# VTM_Ethernet_Module.net
KiCad netlist of a schematic drawn in Altium Designer
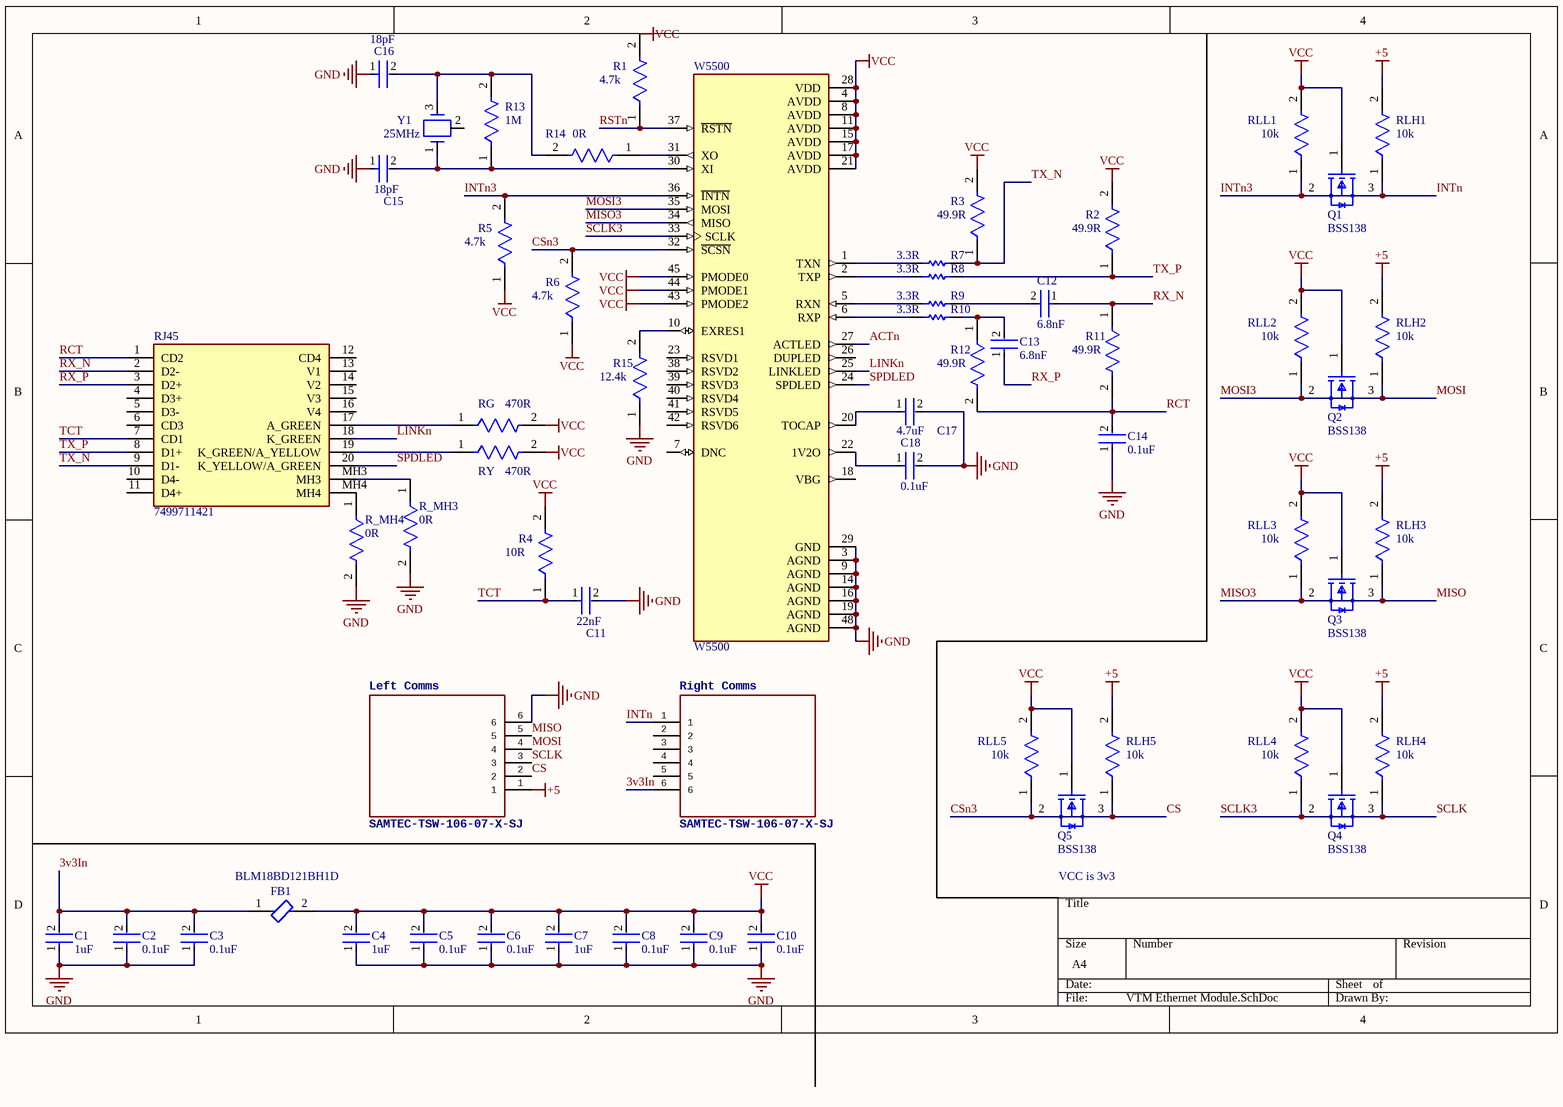
[diagram p0: VTM Ethernet Module.SchDoc]

(export (version "E")
  (design (tool "Eeschema 10.0.6"))
  (components
    (comp (ref "C1")
      (value "1uF")
      (footprint "FP-C0805C-DN-MFG")
      (description "CAP CER 18PF 25V 20% NP0 0805")
      (fields
        (field (name "OCTOPART") "https://octopart.com/c0805c180m3gactu-kemet-17137232")
        (field (name "TOLERANCE") "0.2")
      )
      (libsource (lib "Altium Content Vault") (part "b4654b650e69147ec39a6b967a45e02"))
    )
    (comp (ref "C2")
      (value "0.1uF")
      (footprint "FP-C0805C-DN-MFG")
      (description "CAP CER 18PF 25V 20% NP0 0805")
      (fields
        (field (name "OCTOPART") "https://octopart.com/c0805c180m3gactu-kemet-17137232")
        (field (name "TOLERANCE") "0.2")
      )
      (libsource (lib "Altium Content Vault") (part "b4654b650e69147ec39a6b967a45e02"))
    )
    (comp (ref "C3")
      (value "0.1uF")
      (footprint "FP-C0805C-DN-MFG")
      (description "CAP CER 18PF 25V 20% NP0 0805")
      (fields
        (field (name "OCTOPART") "https://octopart.com/c0805c180m3gactu-kemet-17137232")
        (field (name "TOLERANCE") "0.2")
      )
      (libsource (lib "Altium Content Vault") (part "b4654b650e69147ec39a6b967a45e02"))
    )
    (comp (ref "C4")
      (value "1uF")
      (footprint "FP-C0805C-DN-MFG")
      (description "CAP CER 18PF 25V 20% NP0 0805")
      (fields
        (field (name "OCTOPART") "https://octopart.com/c0805c180m3gactu-kemet-17137232")
        (field (name "TOLERANCE") "0.2")
      )
      (libsource (lib "Altium Content Vault") (part "b4654b650e69147ec39a6b967a45e02"))
    )
    (comp (ref "C5")
      (value "0.1uF")
      (footprint "FP-C0805C-DN-MFG")
      (description "CAP CER 18PF 25V 20% NP0 0805")
      (fields
        (field (name "OCTOPART") "https://octopart.com/c0805c180m3gactu-kemet-17137232")
        (field (name "TOLERANCE") "0.2")
      )
      (libsource (lib "Altium Content Vault") (part "b4654b650e69147ec39a6b967a45e02"))
    )
    (comp (ref "C6")
      (value "0.1uF")
      (footprint "FP-C0805C-DN-MFG")
      (description "CAP CER 18PF 25V 20% NP0 0805")
      (fields
        (field (name "OCTOPART") "https://octopart.com/c0805c180m3gactu-kemet-17137232")
        (field (name "TOLERANCE") "0.2")
      )
      (libsource (lib "Altium Content Vault") (part "b4654b650e69147ec39a6b967a45e02"))
    )
    (comp (ref "C7")
      (value "1uF")
      (footprint "FP-C0805C-DN-MFG")
      (description "CAP CER 18PF 25V 20% NP0 0805")
      (fields
        (field (name "OCTOPART") "https://octopart.com/c0805c180m3gactu-kemet-17137232")
        (field (name "TOLERANCE") "0.2")
      )
      (libsource (lib "Altium Content Vault") (part "b4654b650e69147ec39a6b967a45e02"))
    )
    (comp (ref "C8")
      (value "0.1uF")
      (footprint "FP-C0805C-DN-MFG")
      (description "CAP CER 18PF 25V 20% NP0 0805")
      (fields
        (field (name "OCTOPART") "https://octopart.com/c0805c180m3gactu-kemet-17137232")
        (field (name "TOLERANCE") "0.2")
      )
      (libsource (lib "Altium Content Vault") (part "b4654b650e69147ec39a6b967a45e02"))
    )
    (comp (ref "C9")
      (value "0.1uF")
      (footprint "FP-C0805C-DN-MFG")
      (description "CAP CER 18PF 25V 20% NP0 0805")
      (fields
        (field (name "OCTOPART") "https://octopart.com/c0805c180m3gactu-kemet-17137232")
        (field (name "TOLERANCE") "0.2")
      )
      (libsource (lib "Altium Content Vault") (part "b4654b650e69147ec39a6b967a45e02"))
    )
    (comp (ref "C10")
      (value "0.1uF")
      (footprint "FP-C0805C-DN-MFG")
      (description "CAP CER 18PF 25V 20% NP0 0805")
      (fields
        (field (name "OCTOPART") "https://octopart.com/c0805c180m3gactu-kemet-17137232")
        (field (name "TOLERANCE") "0.2")
      )
      (libsource (lib "Altium Content Vault") (part "b4654b650e69147ec39a6b967a45e02"))
    )
    (comp (ref "C11")
      (value "22nF")
      (footprint "FP-C0805C-DN-MFG")
      (description "CAP CER 18PF 25V 20% NP0 0805")
      (fields
        (field (name "OCTOPART") "https://octopart.com/c0805c180m3gactu-kemet-17137232")
        (field (name "TOLERANCE") "0.2")
      )
      (libsource (lib "Altium Content Vault") (part "b4654b650e69147ec39a6b967a45e02"))
    )
    (comp (ref "C12")
      (value "6.8nF")
      (footprint "FP-C0805C-DN-MFG")
      (description "CAP CER 18PF 25V 20% NP0 0805")
      (fields
        (field (name "OCTOPART") "https://octopart.com/c0805c180m3gactu-kemet-17137232")
        (field (name "TOLERANCE") "0.2")
      )
      (libsource (lib "Altium Content Vault") (part "b4654b650e69147ec39a6b967a45e02"))
    )
    (comp (ref "C13")
      (value "6.8nF")
      (footprint "FP-C0805C-DN-MFG")
      (description "CAP CER 18PF 25V 20% NP0 0805")
      (fields
        (field (name "OCTOPART") "https://octopart.com/c0805c180m3gactu-kemet-17137232")
        (field (name "TOLERANCE") "0.2")
      )
      (libsource (lib "Altium Content Vault") (part "b4654b650e69147ec39a6b967a45e02"))
    )
    (comp (ref "C14")
      (value "0.1uF")
      (footprint "FP-C0805C-DN-MFG")
      (description "CAP CER 18PF 25V 20% NP0 0805")
      (fields
        (field (name "OCTOPART") "https://octopart.com/c0805c180m3gactu-kemet-17137232")
        (field (name "TOLERANCE") "0.2")
      )
      (libsource (lib "Altium Content Vault") (part "b4654b650e69147ec39a6b967a45e02"))
    )
    (comp (ref "C15")
      (value "18pF")
      (footprint "FP-C0805C-DN-MFG")
      (description "CAP CER 18PF 25V 20% NP0 0805")
      (fields
        (field (name "OCTOPART") "https://octopart.com/c0805c180m3gactu-kemet-17137232")
        (field (name "TOLERANCE") "0.2")
      )
      (libsource (lib "Altium Content Vault") (part "b4654b650e69147ec39a6b967a45e02"))
    )
    (comp (ref "C16")
      (value "18pF")
      (footprint "FP-C0805C-DN-MFG")
      (description "CAP CER 18PF 25V 20% NP0 0805")
      (fields
        (field (name "OCTOPART") "https://octopart.com/c0805c180m3gactu-kemet-17137232")
        (field (name "TOLERANCE") "0.2")
      )
      (libsource (lib "Altium Content Vault") (part "b4654b650e69147ec39a6b967a45e02"))
    )
    (comp (ref "C17")
      (value "4.7uF")
      (footprint "FP-C0805C-DN-MFG")
      (description "CAP CER 18PF 25V 20% NP0 0805")
      (fields
        (field (name "OCTOPART") "https://octopart.com/c0805c180m3gactu-kemet-17137232")
        (field (name "TOLERANCE") "0.2")
      )
      (libsource (lib "Altium Content Vault") (part "b4654b650e69147ec39a6b967a45e02"))
    )
    (comp (ref "C18")
      (value "0.1uF")
      (footprint "FP-C0805C-DN-MFG")
      (description "CAP CER 18PF 25V 20% NP0 0805")
      (fields
        (field (name "OCTOPART") "https://octopart.com/c0805c180m3gactu-kemet-17137232")
        (field (name "TOLERANCE") "0.2")
      )
      (libsource (lib "Altium Content Vault") (part "b4654b650e69147ec39a6b967a45e02"))
    )
    (comp (ref "FB1")
      (value "BLM18BD121BH1D")
      (footprint "FP-BLM18-0_15-t0_8-MFG")
      (description "Chip Ferrite Bead, 0603, 120Ω @ 100MHz, 0.4Ω, 25%, 300mA")
      (libsource (lib "Altium Content Vault") (part "5f30dd21d616792df468990f7003faa"))
    )
    (comp (ref "Left Comms")
      (value "SAMTEC-TSW-106-07-X-SJ")
      (footprint "SAMTEC-TSW-106-07-X-S")
      (libsource (lib "TSW-106-07-F-S") (part "SAMTEC-TSW-106-07-X-SJ"))
    )
    (comp (ref "Q1")
      (value "BSS138")
      (footprint "FP-318-08-IPC_B")
      (description "MOSFET N-CH 50V 220MA SOT-23")
      (libsource (lib "Altium Content Vault") (part "3b9c635fedb024a5347a57b145af9cc"))
    )
    (comp (ref "Q2")
      (value "BSS138")
      (footprint "FP-318-08-IPC_B")
      (description "MOSFET N-CH 50V 220MA SOT-23")
      (libsource (lib "Altium Content Vault") (part "3b9c635fedb024a5347a57b145af9cc"))
    )
    (comp (ref "Q3")
      (value "BSS138")
      (footprint "FP-318-08-IPC_B")
      (description "MOSFET N-CH 50V 220MA SOT-23")
      (libsource (lib "Altium Content Vault") (part "3b9c635fedb024a5347a57b145af9cc"))
    )
    (comp (ref "Q4")
      (value "BSS138")
      (footprint "FP-318-08-IPC_B")
      (description "MOSFET N-CH 50V 220MA SOT-23")
      (libsource (lib "Altium Content Vault") (part "3b9c635fedb024a5347a57b145af9cc"))
    )
    (comp (ref "Q5")
      (value "BSS138")
      (footprint "FP-318-08-IPC_B")
      (description "MOSFET N-CH 50V 220MA SOT-23")
      (libsource (lib "Altium Content Vault") (part "3b9c635fedb024a5347a57b145af9cc"))
    )
    (comp (ref "R1")
      (value "4.7k")
      (footprint "FP-CPF0805-MFG")
      (description "RES SMD 1.6M OHM 0.1% 1/10W 0805")
      (fields (field (name "TOLERANCE") "0.1%"))
      (libsource (lib "Altium Content Vault") (part "1029c3af85768c4190bb7ad29bc67b5"))
    )
    (comp (ref "R2")
      (value "49.9R")
      (footprint "FP-CPF0805-MFG")
      (description "RES SMD 1.6M OHM 0.1% 1/10W 0805")
      (fields (field (name "TOLERANCE") "0.1%"))
      (libsource (lib "Altium Content Vault") (part "1029c3af85768c4190bb7ad29bc67b5"))
    )
    (comp (ref "R3")
      (value "49.9R")
      (footprint "FP-CPF0805-MFG")
      (description "RES SMD 1.6M OHM 0.1% 1/10W 0805")
      (fields (field (name "TOLERANCE") "0.1%"))
      (libsource (lib "Altium Content Vault") (part "1029c3af85768c4190bb7ad29bc67b5"))
    )
    (comp (ref "R4")
      (value "10R")
      (footprint "FP-CPF0805-MFG")
      (description "RES SMD 1.6M OHM 0.1% 1/10W 0805")
      (fields (field (name "TOLERANCE") "0.1%"))
      (libsource (lib "Altium Content Vault") (part "1029c3af85768c4190bb7ad29bc67b5"))
    )
    (comp (ref "R5")
      (value "4.7k")
      (footprint "FP-CPF0805-MFG")
      (description "RES SMD 1.6M OHM 0.1% 1/10W 0805")
      (fields (field (name "TOLERANCE") "0.1%"))
      (libsource (lib "Altium Content Vault") (part "1029c3af85768c4190bb7ad29bc67b5"))
    )
    (comp (ref "R6")
      (value "4.7k")
      (footprint "FP-CPF0805-MFG")
      (description "RES SMD 1.6M OHM 0.1% 1/10W 0805")
      (fields (field (name "TOLERANCE") "0.1%"))
      (libsource (lib "Altium Content Vault") (part "1029c3af85768c4190bb7ad29bc67b5"))
    )
    (comp (ref "R7")
      (value "3.3R")
      (footprint "RESC3216X70X50LL05T20")
      (fields (field (name "PART NUMBER") "ERJ-8RQF3R3V") (field (name "MANUFACTURER") "Panasonic"))
      (libsource (lib "Altium Content Vault") (part "RES"))
    )
    (comp (ref "R8")
      (value "3.3R")
      (footprint "RESC3216X70X50LL05T20")
      (fields (field (name "PART NUMBER") "ERJ-8RQF3R3V") (field (name "MANUFACTURER") "Panasonic"))
      (libsource (lib "Altium Content Vault") (part "RES"))
    )
    (comp (ref "R9")
      (value "3.3R")
      (footprint "RESC3216X70X50LL05T20")
      (fields (field (name "PART NUMBER") "ERJ-8RQF3R3V") (field (name "MANUFACTURER") "Panasonic"))
      (libsource (lib "Altium Content Vault") (part "RES"))
    )
    (comp (ref "R10")
      (value "3.3R")
      (footprint "RESC3216X70X50LL05T20")
      (fields (field (name "PART NUMBER") "ERJ-8RQF3R3V") (field (name "MANUFACTURER") "Panasonic"))
      (libsource (lib "Altium Content Vault") (part "RES"))
    )
    (comp (ref "R11")
      (value "49.9R")
      (footprint "FP-CPF0805-MFG")
      (description "RES SMD 1.6M OHM 0.1% 1/10W 0805")
      (fields (field (name "TOLERANCE") "0.1%"))
      (libsource (lib "Altium Content Vault") (part "1029c3af85768c4190bb7ad29bc67b5"))
    )
    (comp (ref "R12")
      (value "49.9R")
      (footprint "FP-CPF0805-MFG")
      (description "RES SMD 1.6M OHM 0.1% 1/10W 0805")
      (fields (field (name "TOLERANCE") "0.1%"))
      (libsource (lib "Altium Content Vault") (part "1029c3af85768c4190bb7ad29bc67b5"))
    )
    (comp (ref "R13")
      (value "1M")
      (footprint "FP-CPF0805-MFG")
      (description "RES SMD 1.6M OHM 0.1% 1/10W 0805")
      (fields (field (name "TOLERANCE") "0.1%"))
      (libsource (lib "Altium Content Vault") (part "1029c3af85768c4190bb7ad29bc67b5"))
    )
    (comp (ref "R14")
      (value "0R")
      (footprint "FP-CPF0805-MFG")
      (description "RES SMD 1.6M OHM 0.1% 1/10W 0805")
      (fields (field (name "TOLERANCE") "0.1%"))
      (libsource (lib "Altium Content Vault") (part "1029c3af85768c4190bb7ad29bc67b5"))
    )
    (comp (ref "R15")
      (value "12.4k")
      (footprint "FP-CPF0805-MFG")
      (description "RES SMD 1.6M OHM 0.1% 1/10W 0805")
      (fields (field (name "TOLERANCE") "0.1%"))
      (libsource (lib "Altium Content Vault") (part "1029c3af85768c4190bb7ad29bc67b5"))
    )
    (comp (ref "RG")
      (value "470R")
      (footprint "FP-CPF0805-MFG")
      (description "RES SMD 1.6M OHM 0.1% 1/10W 0805")
      (fields (field (name "TOLERANCE") "0.1%"))
      (libsource (lib "Altium Content Vault") (part "1029c3af85768c4190bb7ad29bc67b5"))
    )
    (comp (ref "Right Comms")
      (value "SAMTEC-TSW-106-07-X-SJ")
      (footprint "SAMTEC-TSW-106-07-X-S")
      (libsource (lib "TSW-106-07-F-S") (part "SAMTEC-TSW-106-07-X-SJ"))
    )
    (comp (ref "RJ45")
      (value "7499711421")
      (footprint "SamacSys:7499711421")
      (description "Connector")
      (fields (field (name "MOUSER PART NUMBER") "710-7499711421"))
      (libsource (lib "*") (part "7499711421"))
    )
    (comp (ref "RLH1")
      (value "10k")
      (footprint "FP-CPF0805-MFG")
      (description "RES SMD 1.6M OHM 0.1% 1/10W 0805")
      (fields (field (name "TOLERANCE") "0.1%"))
      (libsource (lib "Altium Content Vault") (part "1029c3af85768c4190bb7ad29bc67b5"))
    )
    (comp (ref "RLH2")
      (value "10k")
      (footprint "FP-CPF0805-MFG")
      (description "RES SMD 1.6M OHM 0.1% 1/10W 0805")
      (fields (field (name "TOLERANCE") "0.1%"))
      (libsource (lib "Altium Content Vault") (part "1029c3af85768c4190bb7ad29bc67b5"))
    )
    (comp (ref "RLH3")
      (value "10k")
      (footprint "FP-CPF0805-MFG")
      (description "RES SMD 1.6M OHM 0.1% 1/10W 0805")
      (fields (field (name "TOLERANCE") "0.1%"))
      (libsource (lib "Altium Content Vault") (part "1029c3af85768c4190bb7ad29bc67b5"))
    )
    (comp (ref "RLH4")
      (value "10k")
      (footprint "FP-CPF0805-MFG")
      (description "RES SMD 1.6M OHM 0.1% 1/10W 0805")
      (fields (field (name "TOLERANCE") "0.1%"))
      (libsource (lib "Altium Content Vault") (part "1029c3af85768c4190bb7ad29bc67b5"))
    )
    (comp (ref "RLH5")
      (value "10k")
      (footprint "FP-CPF0805-MFG")
      (description "RES SMD 1.6M OHM 0.1% 1/10W 0805")
      (fields (field (name "TOLERANCE") "0.1%"))
      (libsource (lib "Altium Content Vault") (part "1029c3af85768c4190bb7ad29bc67b5"))
    )
    (comp (ref "RLL1")
      (value "10k")
      (footprint "FP-CPF0805-MFG")
      (description "RES SMD 1.6M OHM 0.1% 1/10W 0805")
      (fields (field (name "TOLERANCE") "0.1%"))
      (libsource (lib "Altium Content Vault") (part "1029c3af85768c4190bb7ad29bc67b5"))
    )
    (comp (ref "RLL2")
      (value "10k")
      (footprint "FP-CPF0805-MFG")
      (description "RES SMD 1.6M OHM 0.1% 1/10W 0805")
      (fields (field (name "TOLERANCE") "0.1%"))
      (libsource (lib "Altium Content Vault") (part "1029c3af85768c4190bb7ad29bc67b5"))
    )
    (comp (ref "RLL3")
      (value "10k")
      (footprint "FP-CPF0805-MFG")
      (description "RES SMD 1.6M OHM 0.1% 1/10W 0805")
      (fields (field (name "TOLERANCE") "0.1%"))
      (libsource (lib "Altium Content Vault") (part "1029c3af85768c4190bb7ad29bc67b5"))
    )
    (comp (ref "RLL4")
      (value "10k")
      (footprint "FP-CPF0805-MFG")
      (description "RES SMD 1.6M OHM 0.1% 1/10W 0805")
      (fields (field (name "TOLERANCE") "0.1%"))
      (libsource (lib "Altium Content Vault") (part "1029c3af85768c4190bb7ad29bc67b5"))
    )
    (comp (ref "RLL5")
      (value "10k")
      (footprint "FP-CPF0805-MFG")
      (description "RES SMD 1.6M OHM 0.1% 1/10W 0805")
      (fields (field (name "TOLERANCE") "0.1%"))
      (libsource (lib "Altium Content Vault") (part "1029c3af85768c4190bb7ad29bc67b5"))
    )
    (comp (ref "RY")
      (value "470R")
      (footprint "FP-CPF0805-MFG")
      (description "RES SMD 1.6M OHM 0.1% 1/10W 0805")
      (fields (field (name "TOLERANCE") "0.1%"))
      (libsource (lib "Altium Content Vault") (part "1029c3af85768c4190bb7ad29bc67b5"))
    )
    (comp (ref "R_MH3")
      (value "0R")
      (footprint "FP-CPF0805-MFG")
      (description "RES SMD 1.6M OHM 0.1% 1/10W 0805")
      (fields (field (name "TOLERANCE") "0.1%"))
      (libsource (lib "Altium Content Vault") (part "1029c3af85768c4190bb7ad29bc67b5"))
    )
    (comp (ref "R_MH4")
      (value "0R")
      (footprint "FP-CPF0805-MFG")
      (description "RES SMD 1.6M OHM 0.1% 1/10W 0805")
      (fields (field (name "TOLERANCE") "0.1%"))
      (libsource (lib "Altium Content Vault") (part "1029c3af85768c4190bb7ad29bc67b5"))
    )
    (comp (ref "W5500")
      (value "W5500")
      (footprint "QFP50P900X900X160-48N")
      (description "Ethernet Controller 10/100 Base-T/TX PHY SPI Interface 48-LQFP (7x7)")
      (fields (field (name "MF") "WIZnet"))
      (libsource (lib "W5500") (part "W5500"))
    )
    (comp (ref "Y1")
      (value "25MHz")
      (footprint "ECS-4X-3IL")
      (description "CRYSTAL 8.00 MHZ 20PF 49US")
      (fields (field (name "PARTNUMBER") "ECS-80-20-4X") (field (name "MANUFACTURER") "ECS"))
      (libsource (lib "Altium Content Vault") (part "ECS-ECS-XX-20-4X"))
    )
  )
  (nets
    (net (code "1") (name "+5") (class "Default")
      (node (ref "Left Comms") (pin "1") (pinfunction "1_1") (pintype "passive"))
      (node (ref "RLH1") (pin "2") (pinfunction "2_2") (pintype "passive"))
      (node (ref "RLH2") (pin "2") (pinfunction "2_2") (pintype "passive"))
      (node (ref "RLH3") (pin "2") (pinfunction "2_2") (pintype "passive"))
      (node (ref "RLH4") (pin "2") (pinfunction "2_2") (pintype "passive"))
      (node (ref "RLH5") (pin "2") (pinfunction "2_2") (pintype "passive"))
    )
    (net (code "2") (name "/3v3In") (class "Default")
      (node (ref "C1") (pin "2") (pinfunction "2_2") (pintype "passive"))
      (node (ref "C2") (pin "2") (pinfunction "2_2") (pintype "passive"))
      (node (ref "C3") (pin "2") (pinfunction "2_2") (pintype "passive"))
      (node (ref "FB1") (pin "1") (pinfunction "1_1") (pintype "passive"))
      (node (ref "Right Comms") (pin "6") (pinfunction "6_6") (pintype "passive"))
    )
    (net (code "3") (name "/ACTn") (class "Default")
      (node (ref "W5500") (pin "27") (pinfunction "ACTLED_27") (pintype "output"))
    )
    (net (code "4") (name "/CS") (class "Default")
      (node (ref "Left Comms") (pin "2") (pinfunction "2_2") (pintype "passive"))
      (node (ref "Q5") (pin "2") (pinfunction "S_2") (pintype "passive"))
      (node (ref "Q5") (pin "3") (pinfunction "D_3") (pintype "passive"))
      (node (ref "R6") (pin "2") (pinfunction "2_2") (pintype "passive"))
      (node (ref "RLH5") (pin "1") (pinfunction "1_1") (pintype "passive"))
      (node (ref "RLL5") (pin "1") (pinfunction "1_1") (pintype "passive"))
      (node (ref "W5500") (pin "32") (pinfunction "~{SCSN}_32") (pintype "input"))
    )
    (net (code "5") (name "/INTn") (class "Default")
      (node (ref "Q1") (pin "2") (pinfunction "S_2") (pintype "passive"))
      (node (ref "Q1") (pin "3") (pinfunction "D_3") (pintype "passive"))
      (node (ref "R5") (pin "2") (pinfunction "2_2") (pintype "passive"))
      (node (ref "RLH1") (pin "1") (pinfunction "1_1") (pintype "passive"))
      (node (ref "RLL1") (pin "1") (pinfunction "1_1") (pintype "passive"))
      (node (ref "Right Comms") (pin "1") (pinfunction "1_1") (pintype "passive"))
      (node (ref "W5500") (pin "36") (pinfunction "~{INTN}_36") (pintype "input"))
    )
    (net (code "6") (name "/LINKn") (class "Default")
      (node (ref "RJ45") (pin "18") (pinfunction "K_GREEN_18") (pintype "passive"))
      (node (ref "W5500") (pin "25") (pinfunction "LINKLED_25") (pintype "output"))
    )
    (net (code "7") (name "/MISO") (class "Default")
      (node (ref "Left Comms") (pin "5") (pinfunction "5_5") (pintype "passive"))
      (node (ref "Q3") (pin "2") (pinfunction "S_2") (pintype "passive"))
      (node (ref "Q3") (pin "3") (pinfunction "D_3") (pintype "passive"))
      (node (ref "RLH3") (pin "1") (pinfunction "1_1") (pintype "passive"))
      (node (ref "RLL3") (pin "1") (pinfunction "1_1") (pintype "passive"))
      (node (ref "W5500") (pin "34") (pinfunction "MISO_34") (pintype "output"))
    )
    (net (code "8") (name "/MOSI") (class "Default")
      (node (ref "Left Comms") (pin "4") (pinfunction "4_4") (pintype "passive"))
      (node (ref "Q2") (pin "2") (pinfunction "S_2") (pintype "passive"))
      (node (ref "Q2") (pin "3") (pinfunction "D_3") (pintype "passive"))
      (node (ref "RLH2") (pin "1") (pinfunction "1_1") (pintype "passive"))
      (node (ref "RLL2") (pin "1") (pinfunction "1_1") (pintype "passive"))
      (node (ref "W5500") (pin "35") (pinfunction "MOSI_35") (pintype "input"))
    )
    (net (code "9") (name "/RCT") (class "Default")
      (node (ref "C14") (pin "2") (pinfunction "2_2") (pintype "passive"))
      (node (ref "R11") (pin "2") (pinfunction "2_2") (pintype "passive"))
      (node (ref "R12") (pin "2") (pinfunction "2_2") (pintype "passive"))
      (node (ref "RJ45") (pin "1") (pinfunction "CD2_1") (pintype "passive"))
    )
    (net (code "10") (name "/RSTn") (class "Default")
      (node (ref "R1") (pin "1") (pinfunction "1_1") (pintype "passive"))
      (node (ref "W5500") (pin "37") (pinfunction "~{RSTN}_37") (pintype "input"))
    )
    (net (code "11") (name "/RX_N") (class "Default")
      (node (ref "C12") (pin "1") (pinfunction "1_1") (pintype "passive"))
      (node (ref "R11") (pin "1") (pinfunction "1_1") (pintype "passive"))
      (node (ref "RJ45") (pin "2") (pinfunction "D2-_2") (pintype "passive"))
    )
    (net (code "12") (name "/RX_P") (class "Default")
      (node (ref "C13") (pin "1") (pinfunction "1_1") (pintype "passive"))
      (node (ref "RJ45") (pin "3") (pinfunction "D2+_3") (pintype "passive"))
    )
    (net (code "13") (name "/SCLK") (class "Default")
      (node (ref "Left Comms") (pin "3") (pinfunction "3_3") (pintype "passive"))
      (node (ref "Q4") (pin "2") (pinfunction "S_2") (pintype "passive"))
      (node (ref "Q4") (pin "3") (pinfunction "D_3") (pintype "passive"))
      (node (ref "RLH4") (pin "1") (pinfunction "1_1") (pintype "passive"))
      (node (ref "RLL4") (pin "1") (pinfunction "1_1") (pintype "passive"))
      (node (ref "W5500") (pin "33") (pinfunction "SCLK_33") (pintype "input"))
    )
    (net (code "14") (name "/SPDLED") (class "Default")
      (node (ref "RJ45") (pin "20") (pinfunction "K_YELLOW/A_GREEN_20") (pintype "passive"))
      (node (ref "W5500") (pin "24") (pinfunction "SPDLED_24") (pintype "output"))
    )
    (net (code "15") (name "/TCT") (class "Default")
      (node (ref "C11") (pin "1") (pinfunction "1_1") (pintype "passive"))
      (node (ref "R4") (pin "1") (pinfunction "1_1") (pintype "passive"))
      (node (ref "RJ45") (pin "7") (pinfunction "CD1_7") (pintype "passive"))
    )
    (net (code "16") (name "/TX_N") (class "Default")
      (node (ref "R3") (pin "1") (pinfunction "1_1") (pintype "passive"))
      (node (ref "R7") (pin "2") (pinfunction "2_2") (pintype "passive"))
      (node (ref "RJ45") (pin "9") (pinfunction "D1-_9") (pintype "passive"))
    )
    (net (code "17") (name "/TX_P") (class "Default")
      (node (ref "R2") (pin "1") (pinfunction "1_1") (pintype "passive"))
      (node (ref "R8") (pin "2") (pinfunction "2_2") (pintype "passive"))
      (node (ref "RJ45") (pin "8") (pinfunction "D1+_8") (pintype "passive"))
    )
    (net (code "18") (name "GND") (class "Default")
      (node (ref "C1") (pin "1") (pinfunction "1_1") (pintype "passive"))
      (node (ref "C10") (pin "1") (pinfunction "1_1") (pintype "passive"))
      (node (ref "C11") (pin "2") (pinfunction "2_2") (pintype "passive"))
      (node (ref "C14") (pin "1") (pinfunction "1_1") (pintype "passive"))
      (node (ref "C15") (pin "1") (pinfunction "1_1") (pintype "passive"))
      (node (ref "C16") (pin "1") (pinfunction "1_1") (pintype "passive"))
      (node (ref "C17") (pin "2") (pinfunction "2_2") (pintype "passive"))
      (node (ref "C18") (pin "2") (pinfunction "2_2") (pintype "passive"))
      (node (ref "C2") (pin "1") (pinfunction "1_1") (pintype "passive"))
      (node (ref "C3") (pin "1") (pinfunction "1_1") (pintype "passive"))
      (node (ref "C4") (pin "1") (pinfunction "1_1") (pintype "passive"))
      (node (ref "C5") (pin "1") (pinfunction "1_1") (pintype "passive"))
      (node (ref "C6") (pin "1") (pinfunction "1_1") (pintype "passive"))
      (node (ref "C7") (pin "1") (pinfunction "1_1") (pintype "passive"))
      (node (ref "C8") (pin "1") (pinfunction "1_1") (pintype "passive"))
      (node (ref "C9") (pin "1") (pinfunction "1_1") (pintype "passive"))
      (node (ref "Left Comms") (pin "6") (pinfunction "6_6") (pintype "passive"))
      (node (ref "R15") (pin "1") (pinfunction "1_1") (pintype "passive"))
      (node (ref "R_MH3") (pin "2") (pinfunction "2_2") (pintype "passive"))
      (node (ref "R_MH4") (pin "2") (pinfunction "2_2") (pintype "passive"))
      (node (ref "W5500") (pin "14") (pinfunction "AGND_14") (pintype "power_in"))
      (node (ref "W5500") (pin "16") (pinfunction "AGND_16") (pintype "power_in"))
      (node (ref "W5500") (pin "19") (pinfunction "AGND_19") (pintype "power_in"))
      (node (ref "W5500") (pin "29") (pinfunction "GND_29") (pintype "passive"))
      (node (ref "W5500") (pin "3") (pinfunction "AGND_3") (pintype "power_in"))
      (node (ref "W5500") (pin "48") (pinfunction "AGND_48") (pintype "power_in"))
      (node (ref "W5500") (pin "9") (pinfunction "AGND_9") (pintype "power_in"))
    )
    (net (code "19") (name "Net-(C12-Pad2)") (class "Default")
      (node (ref "C12") (pin "2") (pinfunction "2_2") (pintype "passive"))
      (node (ref "R9") (pin "2") (pinfunction "2_2") (pintype "passive"))
    )
    (net (code "20") (name "Net-(C13-Pad2)") (class "Default")
      (node (ref "C13") (pin "2") (pinfunction "2_2") (pintype "passive"))
      (node (ref "R10") (pin "2") (pinfunction "2_2") (pintype "passive"))
      (node (ref "R12") (pin "1") (pinfunction "1_1") (pintype "passive"))
    )
    (net (code "21") (name "Net-(C16-Pad2)") (class "Default")
      (node (ref "C16") (pin "2") (pinfunction "2_2") (pintype "passive"))
      (node (ref "R13") (pin "2") (pinfunction "2_2") (pintype "passive"))
      (node (ref "R14") (pin "2") (pinfunction "2_2") (pintype "passive"))
      (node (ref "Y1") (pin "3") (pinfunction "3_3") (pintype "passive"))
    )
    (net (code "22") (name "Net-(RJ45-A_GREEN)") (class "Default")
      (node (ref "RG") (pin "1") (pinfunction "1_1") (pintype "passive"))
      (node (ref "RJ45") (pin "17") (pinfunction "A_GREEN_17") (pintype "passive"))
    )
    (net (code "23") (name "Net-(RJ45-K_GREEN{slash}A_YELLOW)") (class "Default")
      (node (ref "RJ45") (pin "19") (pinfunction "K_GREEN/A_YELLOW_19") (pintype "passive"))
      (node (ref "RY") (pin "1") (pinfunction "1_1") (pintype "passive"))
    )
    (net (code "24") (name "Net-(RJ45-PadMH3)") (class "Default")
      (node (ref "RJ45") (pin "MH3") (pinfunction "MH3_MH3") (pintype "passive"))
      (node (ref "R_MH3") (pin "1") (pinfunction "1_1") (pintype "passive"))
    )
    (net (code "25") (name "Net-(RJ45-PadMH4)") (class "Default")
      (node (ref "RJ45") (pin "MH4") (pinfunction "MH4_MH4") (pintype "passive"))
      (node (ref "R_MH4") (pin "1") (pinfunction "1_1") (pintype "passive"))
    )
    (net (code "26") (name "Net-(W5500-1V2O)") (class "Default")
      (node (ref "C18") (pin "1") (pinfunction "1_1") (pintype "passive"))
      (node (ref "W5500") (pin "22") (pinfunction "1V2O_22") (pintype "output"))
    )
    (net (code "27") (name "Net-(W5500-EXRES1)") (class "Default")
      (node (ref "R15") (pin "2") (pinfunction "2_2") (pintype "passive"))
      (node (ref "W5500") (pin "10") (pinfunction "EXRES1_10") (pintype "bidirectional"))
    )
    (net (code "28") (name "Net-(W5500-RXN)") (class "Default")
      (node (ref "R9") (pin "1") (pinfunction "1_1") (pintype "passive"))
      (node (ref "W5500") (pin "5") (pinfunction "RXN_5") (pintype "input"))
    )
    (net (code "29") (name "Net-(W5500-RXP)") (class "Default")
      (node (ref "R10") (pin "1") (pinfunction "1_1") (pintype "passive"))
      (node (ref "W5500") (pin "6") (pinfunction "RXP_6") (pintype "input"))
    )
    (net (code "30") (name "Net-(W5500-TOCAP)") (class "Default")
      (node (ref "C17") (pin "1") (pinfunction "1_1") (pintype "passive"))
      (node (ref "W5500") (pin "20") (pinfunction "TOCAP_20") (pintype "output"))
    )
    (net (code "31") (name "Net-(W5500-TXN)") (class "Default")
      (node (ref "R7") (pin "1") (pinfunction "1_1") (pintype "passive"))
      (node (ref "W5500") (pin "1") (pinfunction "TXN_1") (pintype "output"))
    )
    (net (code "32") (name "Net-(W5500-TXP)") (class "Default")
      (node (ref "R8") (pin "1") (pinfunction "1_1") (pintype "passive"))
      (node (ref "W5500") (pin "2") (pinfunction "TXP_2") (pintype "output"))
    )
    (net (code "33") (name "Net-(W5500-XI)") (class "Default")
      (node (ref "C15") (pin "2") (pinfunction "2_2") (pintype "passive"))
      (node (ref "R13") (pin "1") (pinfunction "1_1") (pintype "passive"))
      (node (ref "W5500") (pin "30") (pinfunction "XI_30") (pintype "input"))
      (node (ref "Y1") (pin "1") (pinfunction "1_1") (pintype "passive"))
    )
    (net (code "34") (name "Net-(W5500-XO)") (class "Default")
      (node (ref "R14") (pin "1") (pinfunction "1_1") (pintype "passive"))
      (node (ref "W5500") (pin "31") (pinfunction "XO_31") (pintype "output"))
    )
    (net (code "35") (name "VCC") (class "Default")
      (node (ref "C10") (pin "2") (pinfunction "2_2") (pintype "passive"))
      (node (ref "C4") (pin "2") (pinfunction "2_2") (pintype "passive"))
      (node (ref "C5") (pin "2") (pinfunction "2_2") (pintype "passive"))
      (node (ref "C6") (pin "2") (pinfunction "2_2") (pintype "passive"))
      (node (ref "C7") (pin "2") (pinfunction "2_2") (pintype "passive"))
      (node (ref "C8") (pin "2") (pinfunction "2_2") (pintype "passive"))
      (node (ref "C9") (pin "2") (pinfunction "2_2") (pintype "passive"))
      (node (ref "FB1") (pin "2") (pinfunction "2_2") (pintype "passive"))
      (node (ref "Q1") (pin "1") (pinfunction "G_1") (pintype "passive"))
      (node (ref "Q2") (pin "1") (pinfunction "G_1") (pintype "passive"))
      (node (ref "Q3") (pin "1") (pinfunction "G_1") (pintype "passive"))
      (node (ref "Q4") (pin "1") (pinfunction "G_1") (pintype "passive"))
      (node (ref "Q5") (pin "1") (pinfunction "G_1") (pintype "passive"))
      (node (ref "R1") (pin "2") (pinfunction "2_2") (pintype "passive"))
      (node (ref "R2") (pin "2") (pinfunction "2_2") (pintype "passive"))
      (node (ref "R3") (pin "2") (pinfunction "2_2") (pintype "passive"))
      (node (ref "R4") (pin "2") (pinfunction "2_2") (pintype "passive"))
      (node (ref "R5") (pin "1") (pinfunction "1_1") (pintype "passive"))
      (node (ref "R6") (pin "1") (pinfunction "1_1") (pintype "passive"))
      (node (ref "RG") (pin "2") (pinfunction "2_2") (pintype "passive"))
      (node (ref "RLL1") (pin "2") (pinfunction "2_2") (pintype "passive"))
      (node (ref "RLL2") (pin "2") (pinfunction "2_2") (pintype "passive"))
      (node (ref "RLL3") (pin "2") (pinfunction "2_2") (pintype "passive"))
      (node (ref "RLL4") (pin "2") (pinfunction "2_2") (pintype "passive"))
      (node (ref "RLL5") (pin "2") (pinfunction "2_2") (pintype "passive"))
      (node (ref "RY") (pin "2") (pinfunction "2_2") (pintype "passive"))
      (node (ref "W5500") (pin "11") (pinfunction "AVDD_11") (pintype "power_in"))
      (node (ref "W5500") (pin "15") (pinfunction "AVDD_15") (pintype "power_in"))
      (node (ref "W5500") (pin "17") (pinfunction "AVDD_17") (pintype "power_in"))
      (node (ref "W5500") (pin "21") (pinfunction "AVDD_21") (pintype "power_in"))
      (node (ref "W5500") (pin "28") (pinfunction "VDD_28") (pintype "power_in"))
      (node (ref "W5500") (pin "4") (pinfunction "AVDD_4") (pintype "power_in"))
      (node (ref "W5500") (pin "43") (pinfunction "PMODE2_43") (pintype "input"))
      (node (ref "W5500") (pin "44") (pinfunction "PMODE1_44") (pintype "input"))
      (node (ref "W5500") (pin "45") (pinfunction "PMODE0_45") (pintype "input"))
      (node (ref "W5500") (pin "8") (pinfunction "AVDD_8") (pintype "power_in"))
    )
    (net (code "36") (name "unconnected-(RJ45-CD3-Pad6)") (class "Default")
      (node (ref "RJ45") (pin "6") (pinfunction "CD3_6") (pintype "passive"))
    )
    (net (code "37") (name "unconnected-(RJ45-CD4-Pad12)") (class "Default")
      (node (ref "RJ45") (pin "12") (pinfunction "CD4_12") (pintype "passive"))
    )
    (net (code "38") (name "unconnected-(RJ45-D3+-Pad4)") (class "Default")
      (node (ref "RJ45") (pin "4") (pinfunction "D3+_4") (pintype "passive"))
    )
    (net (code "39") (name "unconnected-(RJ45-D3--Pad5)") (class "Default")
      (node (ref "RJ45") (pin "5") (pinfunction "D3-_5") (pintype "passive"))
    )
    (net (code "40") (name "unconnected-(RJ45-D4+-Pad11)") (class "Default")
      (node (ref "RJ45") (pin "11") (pinfunction "D4+_11") (pintype "passive"))
    )
    (net (code "41") (name "unconnected-(RJ45-D4--Pad10)") (class "Default")
      (node (ref "RJ45") (pin "10") (pinfunction "D4-_10") (pintype "passive"))
    )
    (net (code "42") (name "unconnected-(RJ45-V1-Pad13)") (class "Default")
      (node (ref "RJ45") (pin "13") (pinfunction "V1_13") (pintype "passive"))
    )
    (net (code "43") (name "unconnected-(RJ45-V2-Pad14)") (class "Default")
      (node (ref "RJ45") (pin "14") (pinfunction "V2_14") (pintype "passive"))
    )
    (net (code "44") (name "unconnected-(RJ45-V3-Pad15)") (class "Default")
      (node (ref "RJ45") (pin "15") (pinfunction "V3_15") (pintype "passive"))
    )
    (net (code "45") (name "unconnected-(RJ45-V4-Pad16)") (class "Default")
      (node (ref "RJ45") (pin "16") (pinfunction "V4_16") (pintype "passive"))
    )
    (net (code "46") (name "unconnected-(Right Comms-Pad2)") (class "Default")
      (node (ref "Right Comms") (pin "2") (pinfunction "2_2") (pintype "passive"))
    )
    (net (code "47") (name "unconnected-(Right Comms-Pad3)") (class "Default")
      (node (ref "Right Comms") (pin "3") (pinfunction "3_3") (pintype "passive"))
    )
    (net (code "48") (name "unconnected-(Right Comms-Pad4)") (class "Default")
      (node (ref "Right Comms") (pin "4") (pinfunction "4_4") (pintype "passive"))
    )
    (net (code "49") (name "unconnected-(Right Comms-Pad5)") (class "Default")
      (node (ref "Right Comms") (pin "5") (pinfunction "5_5") (pintype "passive"))
    )
    (net (code "50") (name "unconnected-(W5500-DNC-Pad7)") (class "Default")
      (node (ref "W5500") (pin "7") (pinfunction "DNC_7") (pintype "bidirectional"))
    )
    (net (code "51") (name "unconnected-(W5500-DUPLED-Pad26)") (class "Default")
      (node (ref "W5500") (pin "26") (pinfunction "DUPLED_26") (pintype "output"))
    )
    (net (code "52") (name "unconnected-(W5500-RSVD1-Pad23)") (class "Default")
      (node (ref "W5500") (pin "23") (pinfunction "RSVD1_23") (pintype "input"))
    )
    (net (code "53") (name "unconnected-(W5500-RSVD2-Pad38)") (class "Default")
      (node (ref "W5500") (pin "38") (pinfunction "RSVD2_38") (pintype "input"))
    )
    (net (code "54") (name "unconnected-(W5500-RSVD3-Pad39)") (class "Default")
      (node (ref "W5500") (pin "39") (pinfunction "RSVD3_39") (pintype "input"))
    )
    (net (code "55") (name "unconnected-(W5500-RSVD4-Pad40)") (class "Default")
      (node (ref "W5500") (pin "40") (pinfunction "RSVD4_40") (pintype "input"))
    )
    (net (code "56") (name "unconnected-(W5500-RSVD5-Pad41)") (class "Default")
      (node (ref "W5500") (pin "41") (pinfunction "RSVD5_41") (pintype "input"))
    )
    (net (code "57") (name "unconnected-(W5500-RSVD6-Pad42)") (class "Default")
      (node (ref "W5500") (pin "42") (pinfunction "RSVD6_42") (pintype "input"))
    )
    (net (code "58") (name "unconnected-(W5500-VBG-Pad18)") (class "Default")
      (node (ref "W5500") (pin "18") (pinfunction "VBG_18") (pintype "output"))
    )
    (net (code "59") (name "unconnected-(Y1-Pad2)") (class "Default")
      (node (ref "Y1") (pin "2") (pinfunction "2_2") (pintype "passive"))
    )
  )
)
